# dummyvideo.net
KiCad netlist of a schematic drawn in EAGLE
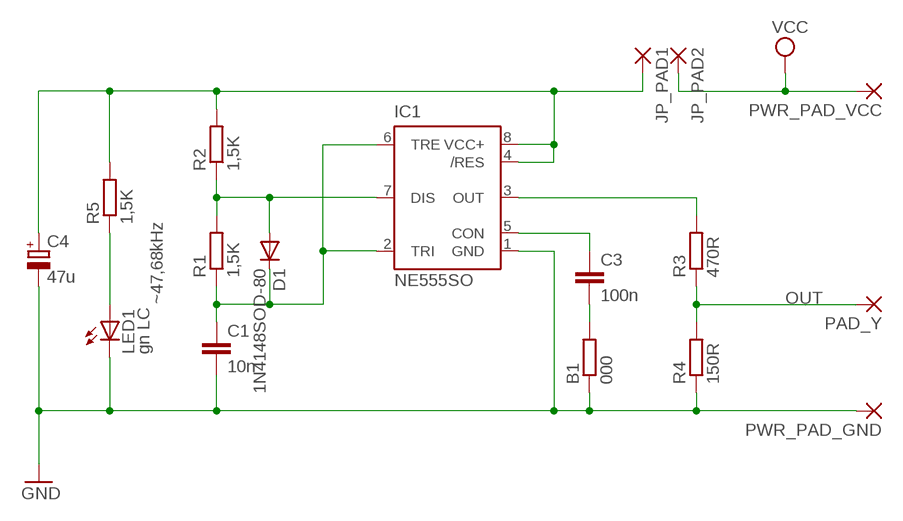
[diagram p0: schematic, sheet 1]

(export (version "E")
  (design (tool "Eeschema 10.0.6"))
  (components
    (comp (ref "B1")
      (value "000")
      (footprint "eagle-import:R1206")
      (libsource (lib "eagle-import") (part "R-EU_R1206"))
    )
    (comp (ref "C1")
      (value "10n")
      (footprint "eagle-import:C0805")
      (libsource (lib "eagle-import") (part "C-EUC0805"))
    )
    (comp (ref "C3")
      (value "100n")
      (footprint "eagle-import:C0805")
      (libsource (lib "eagle-import") (part "C-EUC0805"))
    )
    (comp (ref "C4")
      (value "47u")
      (footprint "eagle-import:153CLV-0505")
      (libsource (lib "eagle-import") (part "CPOL-EU153CLV-0505"))
    )
    (comp (ref "D1")
      (value "1N4148SOD-80")
      (footprint "eagle-import:SOD80C")
      (libsource (lib "eagle-import") (part "1N4148SOD-80"))
    )
    (comp (ref "IC1")
      (value "NE555SO")
      (footprint "eagle-import:SO08")
      (fields (field (name "MPN") "NE555D"))
      (libsource (lib "eagle-import") (part "NE555SO"))
    )
    (comp (ref "JP_PAD1")
      (value "SMD2")
      (footprint "eagle-import:SMD1,27-2,54")
      (libsource (lib "eagle-import") (part "SMD2"))
    )
    (comp (ref "JP_PAD2")
      (value "SMD2")
      (footprint "eagle-import:SMD1,27-2,54")
      (libsource (lib "eagle-import") (part "SMD2"))
    )
    (comp (ref "LED1")
      (value "gn LC")
      (footprint "eagle-import:CHIP-LED0603")
      (libsource (lib "eagle-import") (part "LEDCHIP-LED0603"))
    )
    (comp (ref "PAD_Y")
      (value "SMD2")
      (footprint "eagle-import:SMD1,27-2,54")
      (libsource (lib "eagle-import") (part "SMD2"))
    )
    (comp (ref "PWR_PAD_GND")
      (value "SMD2")
      (footprint "eagle-import:SMD1,27-2,54")
      (libsource (lib "eagle-import") (part "SMD2"))
    )
    (comp (ref "PWR_PAD_VCC")
      (value "SMD2")
      (footprint "eagle-import:SMD1,27-2,54")
      (libsource (lib "eagle-import") (part "SMD2"))
    )
    (comp (ref "R1")
      (value "1,5K")
      (footprint "eagle-import:R0805")
      (libsource (lib "eagle-import") (part "R-EU_R0805"))
    )
    (comp (ref "R2")
      (value "1,5K")
      (footprint "eagle-import:M0805")
      (libsource (lib "eagle-import") (part "R-EU_M0805"))
    )
    (comp (ref "R3")
      (value "470R")
      (footprint "eagle-import:R0805")
      (libsource (lib "eagle-import") (part "R-EU_R0805"))
    )
    (comp (ref "R4")
      (value "150R")
      (footprint "eagle-import:R0805")
      (libsource (lib "eagle-import") (part "R-EU_R0805"))
    )
    (comp (ref "R5")
      (value "1,5K")
      (footprint "eagle-import:R0805")
      (libsource (lib "eagle-import") (part "R-EU_R0805"))
    )
  )
  (nets
    (net (code "1") (name "/OUT") (class "Default")
      (node (ref "PAD_Y") (pin "1") (pinfunction "P_1") (pintype "passive"))
      (node (ref "R3") (pin "1") (pinfunction "1_1") (pintype "passive"))
      (node (ref "R4") (pin "2") (pinfunction "2_2") (pintype "passive"))
    )
    (net (code "2") (name "GND") (class "Default")
      (node (ref "B1") (pin "1") (pinfunction "1_1") (pintype "passive"))
      (node (ref "B1") (pin "2") (pinfunction "2_2") (pintype "passive"))
      (node (ref "C1") (pin "2") (pinfunction "2_2") (pintype "passive"))
      (node (ref "C3") (pin "2") (pinfunction "2_2") (pintype "passive"))
      (node (ref "C4") (pin "-") (pinfunction "-_-") (pintype "passive"))
      (node (ref "IC1") (pin "1") (pinfunction "GND_1") (pintype "power_in"))
      (node (ref "LED1") (pin "C") (pinfunction "C_C") (pintype "passive"))
      (node (ref "PWR_PAD_GND") (pin "1") (pinfunction "P_1") (pintype "passive"))
      (node (ref "R4") (pin "1") (pinfunction "1_1") (pintype "passive"))
    )
    (net (code "3") (name "Net-(IC1-CON)") (class "Default")
      (node (ref "C3") (pin "1") (pinfunction "1_1") (pintype "passive"))
      (node (ref "IC1") (pin "5") (pinfunction "CON_5") (pintype "input"))
    )
    (net (code "4") (name "Net-(IC1-DIS)") (class "Default")
      (node (ref "D1") (pin "A") (pinfunction "A_A") (pintype "passive"))
      (node (ref "IC1") (pin "7") (pinfunction "DIS_7") (pintype "input"))
      (node (ref "R1") (pin "2") (pinfunction "2_2") (pintype "passive"))
      (node (ref "R2") (pin "1") (pinfunction "1_1") (pintype "passive"))
    )
    (net (code "5") (name "Net-(IC1-OUT)") (class "Default")
      (node (ref "IC1") (pin "3") (pinfunction "OUT_3") (pintype "output"))
      (node (ref "R3") (pin "2") (pinfunction "2_2") (pintype "passive"))
    )
    (net (code "6") (name "Net-(IC1-TRE)") (class "Default")
      (node (ref "C1") (pin "1") (pinfunction "1_1") (pintype "passive"))
      (node (ref "D1") (pin "C") (pinfunction "C_C") (pintype "passive"))
      (node (ref "IC1") (pin "2") (pinfunction "TRI_2") (pintype "input"))
      (node (ref "IC1") (pin "6") (pinfunction "TRE_6") (pintype "input"))
      (node (ref "R1") (pin "1") (pinfunction "1_1") (pintype "passive"))
    )
    (net (code "7") (name "Net-(IC1-VCC+)") (class "Default")
      (node (ref "C4") (pin "+") (pinfunction "+_+") (pintype "passive"))
      (node (ref "IC1") (pin "4") (pinfunction "/RES_4") (pintype "input"))
      (node (ref "IC1") (pin "8") (pinfunction "VCC+_8") (pintype "power_in"))
      (node (ref "JP_PAD1") (pin "1") (pinfunction "P_1") (pintype "passive"))
      (node (ref "R2") (pin "2") (pinfunction "2_2") (pintype "passive"))
      (node (ref "R5") (pin "2") (pinfunction "2_2") (pintype "passive"))
    )
    (net (code "8") (name "Net-(LED1-PadA)") (class "Default")
      (node (ref "LED1") (pin "A") (pinfunction "A_A") (pintype "passive"))
      (node (ref "R5") (pin "1") (pinfunction "1_1") (pintype "passive"))
    )
    (net (code "9") (name "VCC") (class "Default")
      (node (ref "JP_PAD2") (pin "1") (pinfunction "P_1") (pintype "passive"))
      (node (ref "PWR_PAD_VCC") (pin "1") (pinfunction "P_1") (pintype "passive"))
    )
  )
)
